# Schematic_esp-firework-firing-system-hw2.net
KiCad netlist of a schematic drawn in EasyEDA
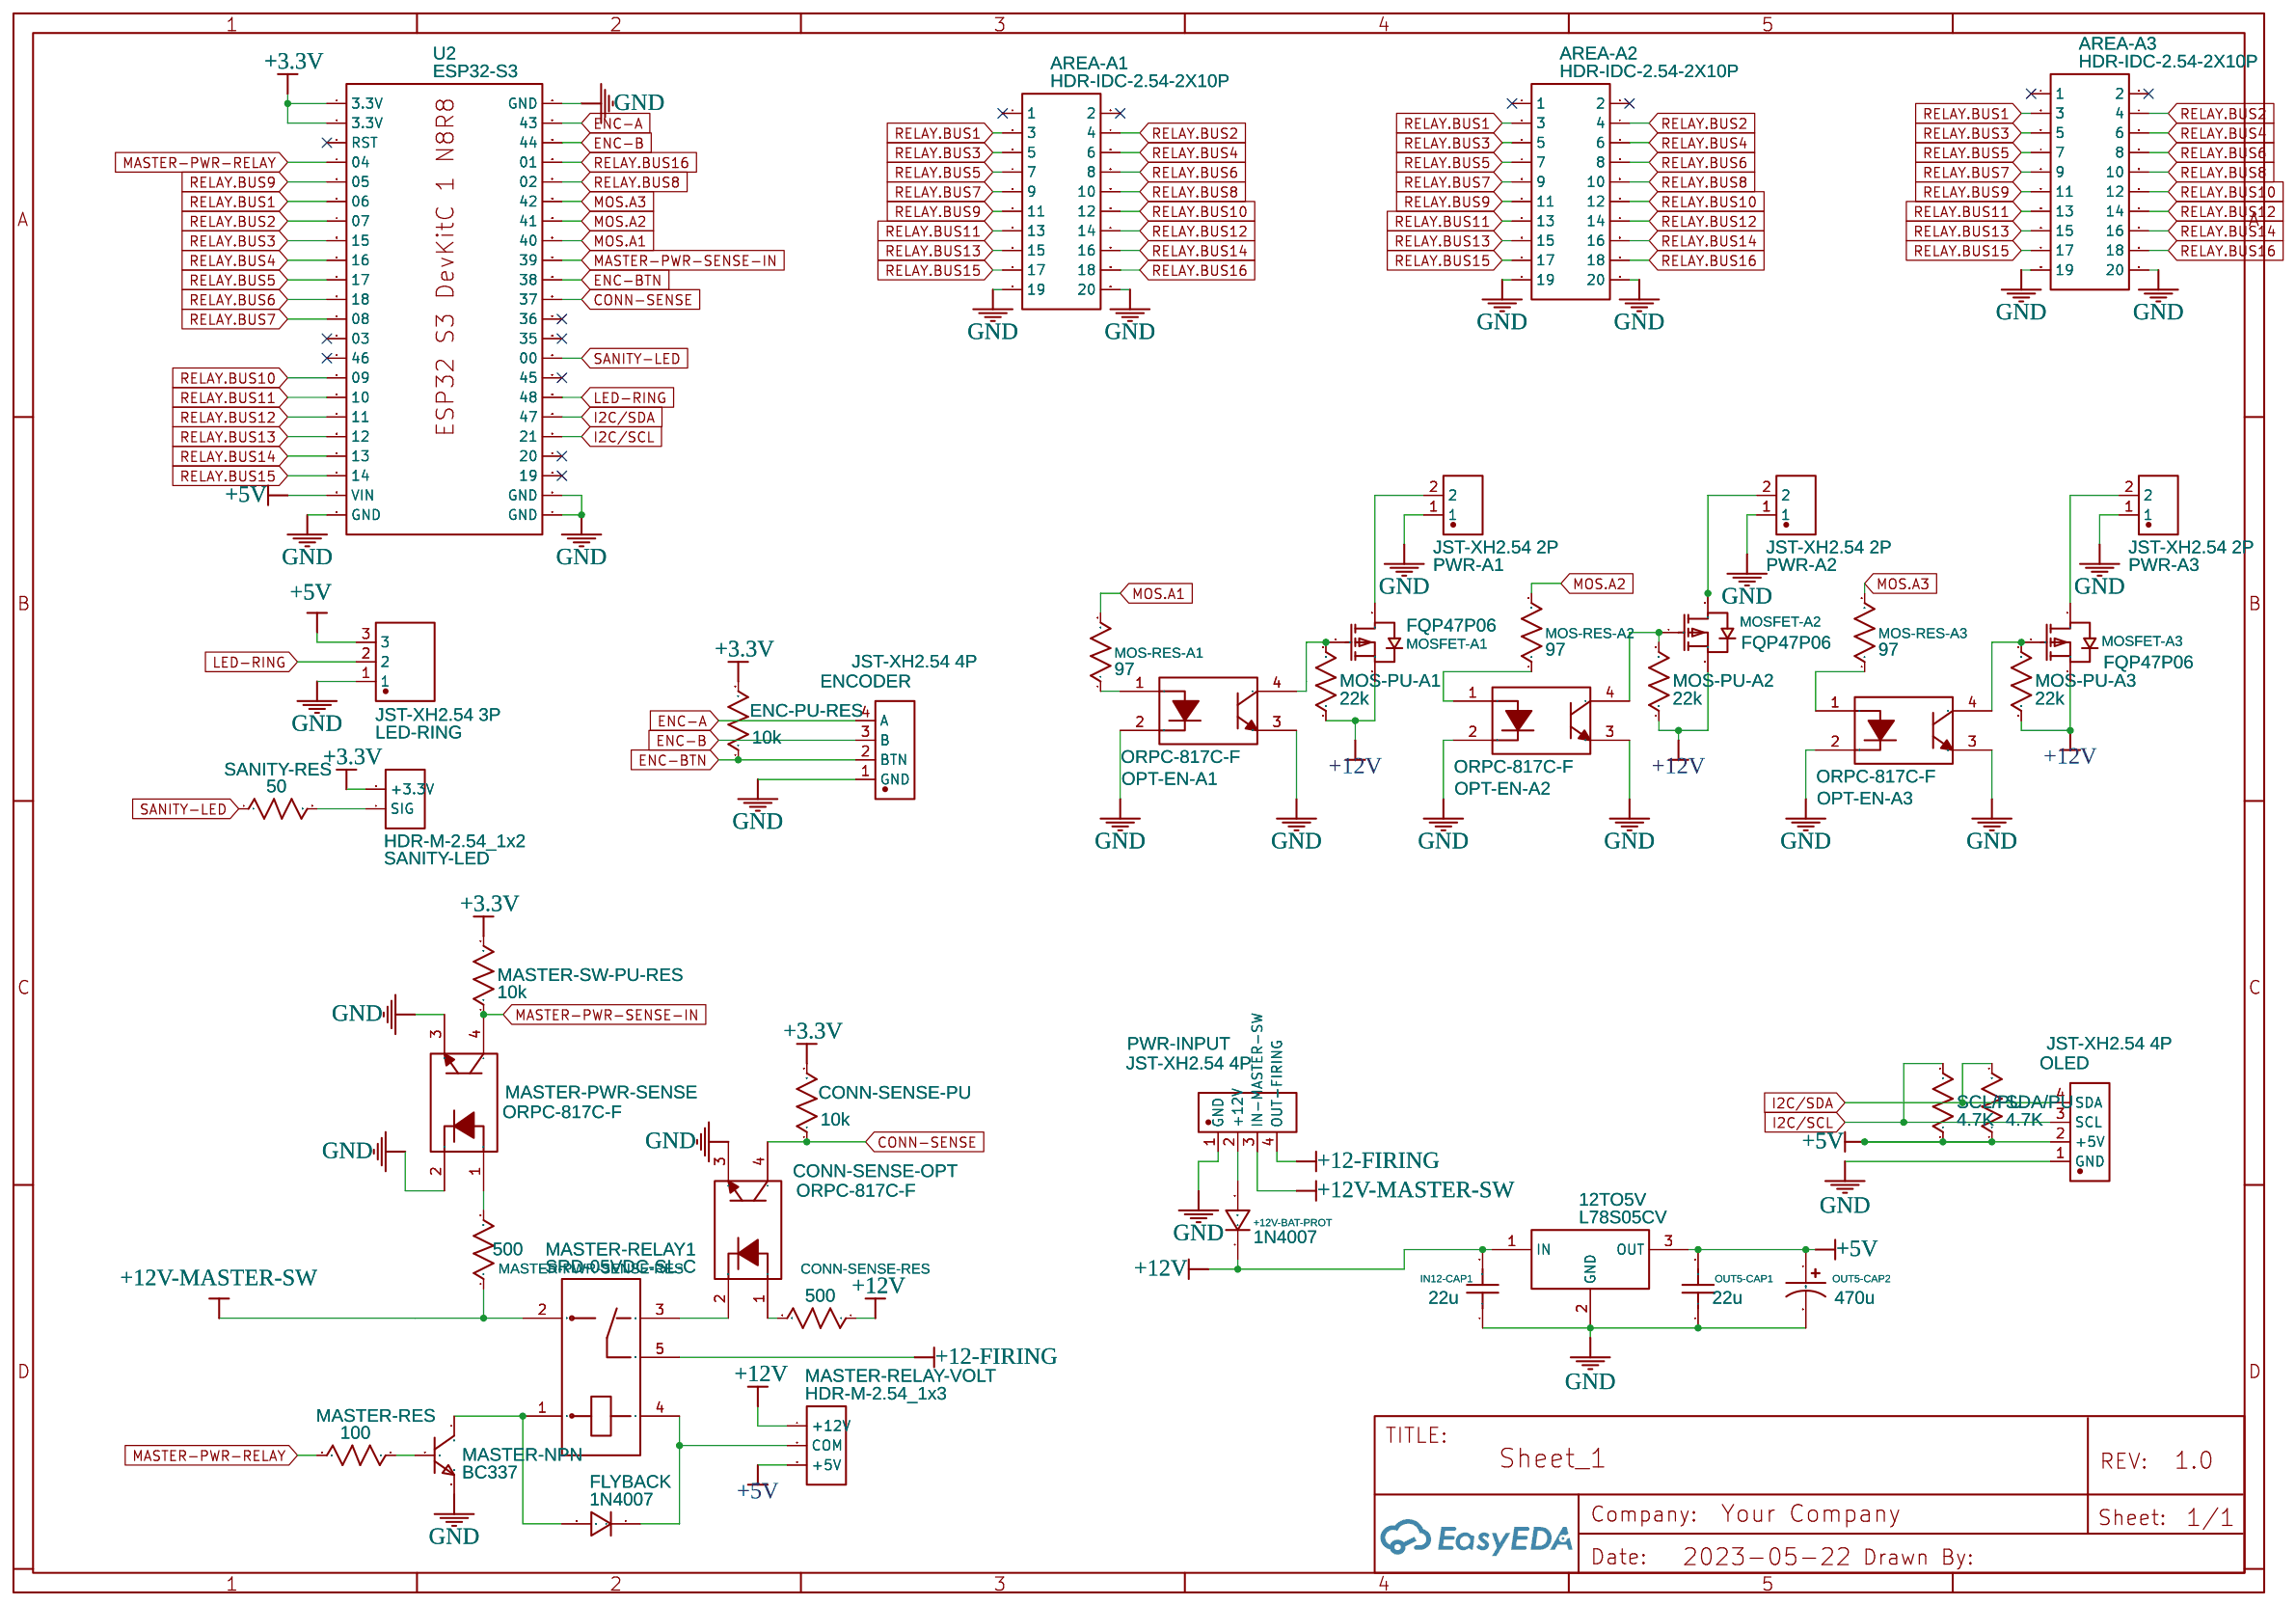
[diagram p0: schematic sheet]

(export (version "E")
  (design (tool "Eeschema 10.0.6"))
  (components
    (comp (ref "+12V-BAT-PROT")
      (value "1N4007")
      (fields (field (name "BOM_Supplier Part") "C106903"))
      (libsource (lib "") (part "1N4007"))
    )
    (comp (ref "12TO5V")
      (value "L78S05CV")
      (fields (field (name "BOM_Supplier Part") "C33043"))
      (libsource (lib "") (part "L78S05CV"))
    )
    (comp (ref "AREA-A1")
      (value "HDR-IDC-2.54-2X10P")
      (fields
        (field (name "BOM_Manufacturer Part") "IDC Box 2.54mm 2X10P　Straight")
        (field (name "BOM_Supplier Part") "C3405")
      )
      (libsource (lib "") (part "HDR-IDC-2.54-2X10P"))
    )
    (comp (ref "AREA-A2")
      (value "HDR-IDC-2.54-2X10P")
      (fields
        (field (name "BOM_Manufacturer Part") "IDC Box 2.54mm 2X10P　Straight")
        (field (name "BOM_Supplier Part") "C3405")
      )
      (libsource (lib "") (part "HDR-IDC-2.54-2X10P"))
    )
    (comp (ref "AREA-A3")
      (value "HDR-IDC-2.54-2X10P")
      (fields
        (field (name "BOM_Manufacturer Part") "IDC Box 2.54mm 2X10P　Straight")
        (field (name "BOM_Supplier Part") "C3405")
      )
      (libsource (lib "") (part "HDR-IDC-2.54-2X10P"))
    )
    (comp (ref "CONN-SENSE-OPT")
      (value "ORPC-817C-F")
      (fields (field (name "BOM_Supplier Part") "C2842770"))
      (libsource (lib "") (part "ORPC-817C-F_1"))
    )
    (comp (ref "CONN-SENSE-PU") (value "10k") (libsource (lib "") (part "R_AXIAL-0.3_US_7")))
    (comp (ref "CONN-SENSE-RES") (value "500") (libsource (lib "") (part "R_AXIAL-0.3_US_1")))
    (comp (ref "ENC-PU-RES") (value "10k") (libsource (lib "") (part "R_AXIAL-0.3_US_2")))
    (comp (ref "ENCODER") (value "JST-XH2.54 4P") (libsource (lib "") (part "JST-XH2.54 4P")))
    (comp (ref "FLYBACK")
      (value "1N4007")
      (fields (field (name "BOM_Supplier Part") "C106903"))
      (libsource (lib "") (part "1N4007_1"))
    )
    (comp (ref "IN12-CAP1") (value "22u") (libsource (lib "") (part "C_RAD-0.1_US")))
    (comp (ref "LED-RING") (value "JST-XH2.54 3P") (libsource (lib "") (part "JST-XH2.54 3P")))
    (comp (ref "MASTER-NPN") (value "BC337") (libsource (lib "") (part "BC337")))
    (comp (ref "MASTER-PWR-SENSE")
      (value "ORPC-817C-F")
      (fields (field (name "BOM_Supplier Part") "C2842770"))
      (libsource (lib "") (part "ORPC-817C-F_2"))
    )
    (comp (ref "MASTER-PWR-SENSE-RES") (value "500") (libsource (lib "") (part "R_AXIAL-0.3_US_10")))
    (comp (ref "MASTER-RELAY-VOLT")
      (value "HDR-M-2.54_1x3")
      (fields (field (name "BOM_Supplier Part") "C180248"))
      (libsource (lib "") (part "HDR-M-2.54_1x3"))
    )
    (comp (ref "MASTER-RELAY1")
      (value "SRD-05VDC-SL-C")
      (fields (field (name "BOM_Supplier Part") "C35449"))
      (libsource (lib "") (part "SRD-05VDC-SL-C"))
    )
    (comp (ref "MASTER-RES") (value "100") (libsource (lib "") (part "R_AXIAL-0.3_US_3")))
    (comp (ref "MASTER-SW-PU-RES") (value "10k") (libsource (lib "") (part "R_AXIAL-0.3_US_9")))
    (comp (ref "MOS-PU-A1") (value "22k") (libsource (lib "") (part "R_AXIAL-0.3_US")))
    (comp (ref "MOS-PU-A2") (value "22k") (libsource (lib "") (part "R_AXIAL-0.3_US")))
    (comp (ref "MOS-PU-A3") (value "22k") (libsource (lib "") (part "R_AXIAL-0.3_US")))
    (comp (ref "MOS-RES-A1") (value "97") (libsource (lib "") (part "R_AXIAL-0.3_US_4")))
    (comp (ref "MOS-RES-A2") (value "97") (libsource (lib "") (part "R_AXIAL-0.3_US_4")))
    (comp (ref "MOS-RES-A3") (value "97") (libsource (lib "") (part "R_AXIAL-0.3_US_4")))
    (comp (ref "MOSFET-A1")
      (value "FQP47P06")
      (fields (field (name "BOM_Supplier Part") "C462765"))
      (libsource (lib "") (part "FQP47P06"))
    )
    (comp (ref "MOSFET-A2")
      (value "FQP47P06")
      (fields (field (name "BOM_Supplier Part") "C462765"))
      (libsource (lib "") (part "FQP47P06"))
    )
    (comp (ref "MOSFET-A3")
      (value "FQP47P06")
      (fields (field (name "BOM_Supplier Part") "C462765"))
      (libsource (lib "") (part "FQP47P06"))
    )
    (comp (ref "OLED") (value "JST-XH2.54 4P") (libsource (lib "") (part "JST-XH2.54 4P_2")))
    (comp (ref "OPT-EN-A1")
      (value "ORPC-817C-F")
      (fields (field (name "BOM_Supplier Part") "C2842770"))
      (libsource (lib "") (part "ORPC-817C-F"))
    )
    (comp (ref "OPT-EN-A2")
      (value "ORPC-817C-F")
      (fields (field (name "BOM_Supplier Part") "C2842770"))
      (libsource (lib "") (part "ORPC-817C-F"))
    )
    (comp (ref "OPT-EN-A3")
      (value "ORPC-817C-F")
      (fields (field (name "BOM_Supplier Part") "C2842770"))
      (libsource (lib "") (part "ORPC-817C-F"))
    )
    (comp (ref "OUT5-CAP1") (value "22u") (libsource (lib "") (part "C_RAD-0.1_US_1")))
    (comp (ref "OUT5-CAP2") (value "470u") (libsource (lib "") (part "CE_TH_D6.3×F2.5_US")))
    (comp (ref "PWR-A1") (value "JST-XH2.54 2P") (libsource (lib "") (part "JST-XH2.54 2P")))
    (comp (ref "PWR-A2") (value "JST-XH2.54 2P") (libsource (lib "") (part "JST-XH2.54 2P")))
    (comp (ref "PWR-A3") (value "JST-XH2.54 2P") (libsource (lib "") (part "JST-XH2.54 2P")))
    (comp (ref "PWR-INPUT") (value "JST-XH2.54 4P") (libsource (lib "") (part "JST-XH2.54 4P_1")))
    (comp (ref "SANITY-LED")
      (value "HDR-M-2.54_1x2")
      (fields (field (name "BOM_Supplier Part") "C124375"))
      (libsource (lib "") (part "HDR-M-2.54_1x2"))
    )
    (comp (ref "SANITY-RES") (value "50") (libsource (lib "") (part "R_AXIAL-0.3_US_8")))
    (comp (ref "SCL/PU") (value "4.7K") (libsource (lib "") (part "R_AXIAL-0.3_US_5")))
    (comp (ref "SDA/PU") (value "4.7K") (libsource (lib "") (part "R_AXIAL-0.3_US_6")))
    (comp (ref "U2") (value "ESP32-S3") (libsource (lib "") (part "ESP32-S3")))
  )
  (nets
    (net (code "1") (name "+3.3V") (class "Default")
      (node (ref "CONN-SENSE-PU") (pin "2") (pinfunction "2_2") (pintype "unspecified"))
      (node (ref "ENC-PU-RES") (pin "2") (pinfunction "2_2") (pintype "unspecified"))
      (node (ref "MASTER-SW-PU-RES") (pin "2") (pinfunction "2_2") (pintype "unspecified"))
      (node (ref "SANITY-LED") (pin "2") (pinfunction "+3.3V_2") (pintype "unspecified"))
      (node (ref "U2") (pin "1") (pinfunction "3.3V_1") (pintype "unspecified"))
      (node (ref "U2") (pin "2") (pinfunction "3.3V_2") (pintype "unspecified"))
    )
    (net (code "2") (name "+5V") (class "Default")
      (node (ref "12TO5V") (pin "3") (pinfunction "OUT_3") (pintype "passive"))
      (node (ref "LED-RING") (pin "3") (pinfunction "3_3") (pintype "unspecified"))
      (node (ref "MASTER-RELAY-VOLT") (pin "3") (pinfunction "+5V_3") (pintype "input"))
      (node (ref "OLED") (pin "2") (pinfunction "+5V_2") (pintype "unspecified"))
      (node (ref "OUT5-CAP1") (pin "2") (pinfunction "2_2") (pintype "unspecified"))
      (node (ref "OUT5-CAP2") (pin "1") (pinfunction "1_1") (pintype "unspecified"))
      (node (ref "SCL/PU") (pin "1") (pinfunction "1_1") (pintype "unspecified"))
      (node (ref "SDA/PU") (pin "1") (pinfunction "1_1") (pintype "unspecified"))
      (node (ref "U2") (pin "21") (pinfunction "VIN_21") (pintype "unspecified"))
    )
    (net (code "3") (name "+12-FIRING") (class "Default")
      (node (ref "MASTER-RELAY1") (pin "5") (pinfunction "5_5") (pintype "input"))
      (node (ref "PWR-INPUT") (pin "4") (pinfunction "OUT-FIRING_4") (pintype "unspecified"))
    )
    (net (code "4") (name "+12V") (class "Default")
      (node (ref "+12V-BAT-PROT") (pin "1") (pinfunction "1_1") (pintype "unspecified"))
      (node (ref "12TO5V") (pin "1") (pinfunction "IN_1") (pintype "passive"))
      (node (ref "CONN-SENSE-RES") (pin "1") (pinfunction "1_1") (pintype "unspecified"))
      (node (ref "IN12-CAP1") (pin "2") (pinfunction "2_2") (pintype "unspecified"))
      (node (ref "MASTER-RELAY-VOLT") (pin "1") (pinfunction "+12V_1") (pintype "input"))
      (node (ref "MOS-PU-A1") (pin "1") (pinfunction "1_1") (pintype "unspecified"))
      (node (ref "MOS-PU-A2") (pin "1") (pinfunction "1_1") (pintype "unspecified"))
      (node (ref "MOS-PU-A3") (pin "1") (pinfunction "1_1") (pintype "unspecified"))
      (node (ref "MOSFET-A1") (pin "3") (pinfunction "S_3") (pintype "unspecified"))
      (node (ref "MOSFET-A2") (pin "3") (pinfunction "S_3") (pintype "unspecified"))
      (node (ref "MOSFET-A3") (pin "3") (pinfunction "S_3") (pintype "unspecified"))
    )
    (net (code "5") (name "+12V-MASTER-SW") (class "Default")
      (node (ref "MASTER-PWR-SENSE-RES") (pin "1") (pinfunction "1_1") (pintype "unspecified"))
      (node (ref "MASTER-RELAY1") (pin "2") (pinfunction "2_2") (pintype "input"))
      (node (ref "PWR-INPUT") (pin "3") (pinfunction "IN-MASTER-SW_3") (pintype "unspecified"))
    )
    (net (code "6") (name "CONN-SENSE") (class "Default")
      (node (ref "CONN-SENSE-OPT") (pin "4") (pinfunction "4_4") (pintype "unspecified"))
      (node (ref "CONN-SENSE-PU") (pin "1") (pinfunction "1_1") (pintype "unspecified"))
      (node (ref "U2") (pin "33") (pinfunction "37_33") (pintype "unspecified"))
    )
    (net (code "7") (name "ENC-A") (class "Default")
      (node (ref "ENCODER") (pin "4") (pinfunction "A_4") (pintype "unspecified"))
      (node (ref "U2") (pin "24") (pinfunction "43_24") (pintype "unspecified"))
    )
    (net (code "8") (name "ENC-B") (class "Default")
      (node (ref "ENCODER") (pin "3") (pinfunction "B_3") (pintype "unspecified"))
      (node (ref "U2") (pin "25") (pinfunction "44_25") (pintype "unspecified"))
    )
    (net (code "9") (name "ENC-BTN") (class "Default")
      (node (ref "ENC-PU-RES") (pin "1") (pinfunction "1_1") (pintype "unspecified"))
      (node (ref "ENCODER") (pin "2") (pinfunction "BTN_2") (pintype "unspecified"))
      (node (ref "U2") (pin "32") (pinfunction "38_32") (pintype "unspecified"))
    )
    (net (code "10") (name "GND") (class "Default")
      (node (ref "12TO5V") (pin "2") (pinfunction "GND_2") (pintype "passive"))
      (node (ref "AREA-A1") (pin "19") (pinfunction "19_19") (pintype "unspecified"))
      (node (ref "AREA-A1") (pin "20") (pinfunction "20_20") (pintype "unspecified"))
      (node (ref "AREA-A2") (pin "19") (pinfunction "19_19") (pintype "unspecified"))
      (node (ref "AREA-A2") (pin "20") (pinfunction "20_20") (pintype "unspecified"))
      (node (ref "AREA-A3") (pin "19") (pinfunction "19_19") (pintype "unspecified"))
      (node (ref "AREA-A3") (pin "20") (pinfunction "20_20") (pintype "unspecified"))
      (node (ref "CONN-SENSE-OPT") (pin "3") (pinfunction "3_3") (pintype "unspecified"))
      (node (ref "ENCODER") (pin "1") (pinfunction "GND_1") (pintype "unspecified"))
      (node (ref "IN12-CAP1") (pin "1") (pinfunction "1_1") (pintype "unspecified"))
      (node (ref "LED-RING") (pin "1") (pinfunction "1_1") (pintype "unspecified"))
      (node (ref "MASTER-NPN") (pin "3") (pinfunction "E_3") (pintype "unspecified"))
      (node (ref "MASTER-PWR-SENSE") (pin "2") (pinfunction "2_2") (pintype "unspecified"))
      (node (ref "MASTER-PWR-SENSE") (pin "3") (pinfunction "3_3") (pintype "unspecified"))
      (node (ref "OLED") (pin "1") (pinfunction "GND_1") (pintype "unspecified"))
      (node (ref "OPT-EN-A1") (pin "2") (pinfunction "2_2") (pintype "unspecified"))
      (node (ref "OPT-EN-A1") (pin "3") (pinfunction "3_3") (pintype "unspecified"))
      (node (ref "OPT-EN-A2") (pin "2") (pinfunction "2_2") (pintype "unspecified"))
      (node (ref "OPT-EN-A2") (pin "3") (pinfunction "3_3") (pintype "unspecified"))
      (node (ref "OPT-EN-A3") (pin "2") (pinfunction "2_2") (pintype "unspecified"))
      (node (ref "OPT-EN-A3") (pin "3") (pinfunction "3_3") (pintype "unspecified"))
      (node (ref "OUT5-CAP1") (pin "1") (pinfunction "1_1") (pintype "unspecified"))
      (node (ref "OUT5-CAP2") (pin "2") (pinfunction "2_2") (pintype "unspecified"))
      (node (ref "PWR-A1") (pin "1") (pinfunction "1_1") (pintype "unspecified"))
      (node (ref "PWR-A2") (pin "1") (pinfunction "1_1") (pintype "unspecified"))
      (node (ref "PWR-A3") (pin "1") (pinfunction "1_1") (pintype "unspecified"))
      (node (ref "PWR-INPUT") (pin "1") (pinfunction "GND_1") (pintype "unspecified"))
      (node (ref "U2") (pin "22") (pinfunction "GND_22") (pintype "unspecified"))
      (node (ref "U2") (pin "23") (pinfunction "GND_23") (pintype "unspecified"))
      (node (ref "U2") (pin "43") (pinfunction "GND_43") (pintype "unspecified"))
      (node (ref "U2") (pin "44") (pinfunction "GND_44") (pintype "unspecified"))
    )
    (net (code "11") (name "I2C{slash}SCL") (class "Default")
      (node (ref "OLED") (pin "3") (pinfunction "SCL_3") (pintype "unspecified"))
      (node (ref "SCL/PU") (pin "2") (pinfunction "2_2") (pintype "unspecified"))
      (node (ref "U2") (pin "40") (pinfunction "21_40") (pintype "unspecified"))
    )
    (net (code "12") (name "I2C{slash}SDA") (class "Default")
      (node (ref "OLED") (pin "4") (pinfunction "SDA_4") (pintype "unspecified"))
      (node (ref "SDA/PU") (pin "2") (pinfunction "2_2") (pintype "unspecified"))
      (node (ref "U2") (pin "39") (pinfunction "47_39") (pintype "unspecified"))
    )
    (net (code "13") (name "LED-RING") (class "Default")
      (node (ref "LED-RING") (pin "2") (pinfunction "2_2") (pintype "unspecified"))
      (node (ref "U2") (pin "38") (pinfunction "48_38") (pintype "unspecified"))
    )
    (net (code "14") (name "MASTER-PWR-RELAY") (class "Default")
      (node (ref "MASTER-RES") (pin "2") (pinfunction "2_2") (pintype "unspecified"))
      (node (ref "U2") (pin "4") (pinfunction "04_4") (pintype "unspecified"))
    )
    (net (code "15") (name "MASTER-PWR-SENSE-IN") (class "Default")
      (node (ref "MASTER-PWR-SENSE") (pin "4") (pinfunction "4_4") (pintype "unspecified"))
      (node (ref "MASTER-SW-PU-RES") (pin "1") (pinfunction "1_1") (pintype "unspecified"))
      (node (ref "U2") (pin "31") (pinfunction "39_31") (pintype "unspecified"))
    )
    (net (code "16") (name "MOS.A1") (class "Default")
      (node (ref "MOS-RES-A1") (pin "2") (pinfunction "2_2") (pintype "unspecified"))
      (node (ref "U2") (pin "30") (pinfunction "40_30") (pintype "unspecified"))
    )
    (net (code "17") (name "MOS.A2") (class "Default")
      (node (ref "MOS-RES-A2") (pin "2") (pinfunction "2_2") (pintype "unspecified"))
      (node (ref "U2") (pin "29") (pinfunction "41_29") (pintype "unspecified"))
    )
    (net (code "18") (name "MOS.A3") (class "Default")
      (node (ref "MOS-RES-A3") (pin "2") (pinfunction "2_2") (pintype "unspecified"))
      (node (ref "U2") (pin "28") (pinfunction "42_28") (pintype "unspecified"))
    )
    (net (code "19") (name "Net-(CONN-SENSE-OPT-Pad1)") (class "Default")
      (node (ref "CONN-SENSE-OPT") (pin "1") (pinfunction "1_1") (pintype "unspecified"))
      (node (ref "CONN-SENSE-RES") (pin "2") (pinfunction "2_2") (pintype "unspecified"))
    )
    (net (code "20") (name "Net-(CONN-SENSE-OPT-Pad2)") (class "Default")
      (node (ref "CONN-SENSE-OPT") (pin "2") (pinfunction "2_2") (pintype "unspecified"))
      (node (ref "MASTER-RELAY1") (pin "3") (pinfunction "3_3") (pintype "input"))
    )
    (net (code "21") (name "Net-(MASTER-NPN-B)") (class "Default")
      (node (ref "MASTER-NPN") (pin "2") (pinfunction "B_2") (pintype "unspecified"))
      (node (ref "MASTER-RES") (pin "1") (pinfunction "1_1") (pintype "unspecified"))
    )
    (net (code "22") (name "Net-(MASTER-NPN-C)") (class "Default")
      (node (ref "FLYBACK") (pin "2") (pinfunction "2_2") (pintype "unspecified"))
      (node (ref "MASTER-NPN") (pin "1") (pinfunction "C_1") (pintype "unspecified"))
      (node (ref "MASTER-RELAY1") (pin "1") (pinfunction "1_1") (pintype "input"))
    )
    (net (code "23") (name "Net-(MASTER-PWR-SENSE-Pad1)") (class "Default")
      (node (ref "MASTER-PWR-SENSE") (pin "1") (pinfunction "1_1") (pintype "unspecified"))
      (node (ref "MASTER-PWR-SENSE-RES") (pin "2") (pinfunction "2_2") (pintype "unspecified"))
    )
    (net (code "24") (name "Net-(MASTER-RELAY-VOLT-COM)") (class "Default")
      (node (ref "FLYBACK") (pin "1") (pinfunction "1_1") (pintype "unspecified"))
      (node (ref "MASTER-RELAY-VOLT") (pin "2") (pinfunction "COM_2") (pintype "input"))
      (node (ref "MASTER-RELAY1") (pin "4") (pinfunction "4_4") (pintype "input"))
    )
    (net (code "25") (name "Net-(MOS-RES-A1-Pad1)") (class "Default")
      (node (ref "MOS-RES-A1") (pin "1") (pinfunction "1_1") (pintype "unspecified"))
      (node (ref "OPT-EN-A1") (pin "1") (pinfunction "1_1") (pintype "unspecified"))
    )
    (net (code "26") (name "Net-(MOS-RES-A2-Pad1)") (class "Default")
      (node (ref "MOS-RES-A2") (pin "1") (pinfunction "1_1") (pintype "unspecified"))
      (node (ref "OPT-EN-A2") (pin "1") (pinfunction "1_1") (pintype "unspecified"))
    )
    (net (code "27") (name "Net-(MOS-RES-A3-Pad1)") (class "Default")
      (node (ref "MOS-RES-A3") (pin "1") (pinfunction "1_1") (pintype "unspecified"))
      (node (ref "OPT-EN-A3") (pin "1") (pinfunction "1_1") (pintype "unspecified"))
    )
    (net (code "28") (name "Net-(MOSFET-A1-D)") (class "Default")
      (node (ref "MOSFET-A1") (pin "2") (pinfunction "D_2") (pintype "unspecified"))
      (node (ref "PWR-A1") (pin "2") (pinfunction "2_2") (pintype "unspecified"))
    )
    (net (code "29") (name "Net-(MOSFET-A1-G)") (class "Default")
      (node (ref "MOS-PU-A1") (pin "2") (pinfunction "2_2") (pintype "unspecified"))
      (node (ref "MOSFET-A1") (pin "1") (pinfunction "G_1") (pintype "unspecified"))
      (node (ref "OPT-EN-A1") (pin "4") (pinfunction "4_4") (pintype "unspecified"))
    )
    (net (code "30") (name "Net-(MOSFET-A2-D)") (class "Default")
      (node (ref "MOSFET-A2") (pin "2") (pinfunction "D_2") (pintype "unspecified"))
      (node (ref "PWR-A2") (pin "2") (pinfunction "2_2") (pintype "unspecified"))
    )
    (net (code "31") (name "Net-(MOSFET-A2-G)") (class "Default")
      (node (ref "MOS-PU-A2") (pin "2") (pinfunction "2_2") (pintype "unspecified"))
      (node (ref "MOSFET-A2") (pin "1") (pinfunction "G_1") (pintype "unspecified"))
      (node (ref "OPT-EN-A2") (pin "4") (pinfunction "4_4") (pintype "unspecified"))
    )
    (net (code "32") (name "Net-(MOSFET-A3-D)") (class "Default")
      (node (ref "MOSFET-A3") (pin "2") (pinfunction "D_2") (pintype "unspecified"))
      (node (ref "PWR-A3") (pin "2") (pinfunction "2_2") (pintype "unspecified"))
    )
    (net (code "33") (name "Net-(MOSFET-A3-G)") (class "Default")
      (node (ref "MOS-PU-A3") (pin "2") (pinfunction "2_2") (pintype "unspecified"))
      (node (ref "MOSFET-A3") (pin "1") (pinfunction "G_1") (pintype "unspecified"))
      (node (ref "OPT-EN-A3") (pin "4") (pinfunction "4_4") (pintype "unspecified"))
    )
    (net (code "34") (name "Net-(PWR-INPUT-+12V)") (class "Default")
      (node (ref "+12V-BAT-PROT") (pin "2") (pinfunction "2_2") (pintype "unspecified"))
      (node (ref "PWR-INPUT") (pin "2") (pinfunction "+12V_2") (pintype "unspecified"))
    )
    (net (code "35") (name "Net-(SANITY-LED-SIG)") (class "Default")
      (node (ref "SANITY-LED") (pin "1") (pinfunction "SIG_1") (pintype "unspecified"))
      (node (ref "SANITY-RES") (pin "2") (pinfunction "2_2") (pintype "unspecified"))
    )
    (net (code "36") (name "RELAY.BUS1") (class "Default")
      (node (ref "AREA-A1") (pin "3") (pinfunction "3_3") (pintype "unspecified"))
      (node (ref "AREA-A2") (pin "3") (pinfunction "3_3") (pintype "unspecified"))
      (node (ref "AREA-A3") (pin "3") (pinfunction "3_3") (pintype "unspecified"))
      (node (ref "U2") (pin "6") (pinfunction "06_6") (pintype "unspecified"))
    )
    (net (code "37") (name "RELAY.BUS2") (class "Default")
      (node (ref "AREA-A1") (pin "4") (pinfunction "4_4") (pintype "unspecified"))
      (node (ref "AREA-A2") (pin "4") (pinfunction "4_4") (pintype "unspecified"))
      (node (ref "AREA-A3") (pin "4") (pinfunction "4_4") (pintype "unspecified"))
      (node (ref "U2") (pin "7") (pinfunction "07_7") (pintype "unspecified"))
    )
    (net (code "38") (name "RELAY.BUS3") (class "Default")
      (node (ref "AREA-A1") (pin "5") (pinfunction "5_5") (pintype "unspecified"))
      (node (ref "AREA-A2") (pin "5") (pinfunction "5_5") (pintype "unspecified"))
      (node (ref "AREA-A3") (pin "5") (pinfunction "5_5") (pintype "unspecified"))
      (node (ref "U2") (pin "8") (pinfunction "15_8") (pintype "unspecified"))
    )
    (net (code "39") (name "RELAY.BUS4") (class "Default")
      (node (ref "AREA-A1") (pin "6") (pinfunction "6_6") (pintype "unspecified"))
      (node (ref "AREA-A2") (pin "6") (pinfunction "6_6") (pintype "unspecified"))
      (node (ref "AREA-A3") (pin "6") (pinfunction "6_6") (pintype "unspecified"))
      (node (ref "U2") (pin "9") (pinfunction "16_9") (pintype "unspecified"))
    )
    (net (code "40") (name "RELAY.BUS5") (class "Default")
      (node (ref "AREA-A1") (pin "7") (pinfunction "7_7") (pintype "unspecified"))
      (node (ref "AREA-A2") (pin "7") (pinfunction "7_7") (pintype "unspecified"))
      (node (ref "AREA-A3") (pin "7") (pinfunction "7_7") (pintype "unspecified"))
      (node (ref "U2") (pin "10") (pinfunction "17_10") (pintype "unspecified"))
    )
    (net (code "41") (name "RELAY.BUS6") (class "Default")
      (node (ref "AREA-A1") (pin "8") (pinfunction "8_8") (pintype "unspecified"))
      (node (ref "AREA-A2") (pin "8") (pinfunction "8_8") (pintype "unspecified"))
      (node (ref "AREA-A3") (pin "8") (pinfunction "8_8") (pintype "unspecified"))
      (node (ref "U2") (pin "11") (pinfunction "18_11") (pintype "unspecified"))
    )
    (net (code "42") (name "RELAY.BUS7") (class "Default")
      (node (ref "AREA-A1") (pin "9") (pinfunction "9_9") (pintype "unspecified"))
      (node (ref "AREA-A2") (pin "9") (pinfunction "9_9") (pintype "unspecified"))
      (node (ref "AREA-A3") (pin "9") (pinfunction "9_9") (pintype "unspecified"))
      (node (ref "U2") (pin "12") (pinfunction "08_12") (pintype "unspecified"))
    )
    (net (code "43") (name "RELAY.BUS8") (class "Default")
      (node (ref "AREA-A1") (pin "10") (pinfunction "10_10") (pintype "unspecified"))
      (node (ref "AREA-A2") (pin "10") (pinfunction "10_10") (pintype "unspecified"))
      (node (ref "AREA-A3") (pin "10") (pinfunction "10_10") (pintype "unspecified"))
      (node (ref "U2") (pin "27") (pinfunction "02_27") (pintype "unspecified"))
    )
    (net (code "44") (name "RELAY.BUS9") (class "Default")
      (node (ref "AREA-A1") (pin "11") (pinfunction "11_11") (pintype "unspecified"))
      (node (ref "AREA-A2") (pin "11") (pinfunction "11_11") (pintype "unspecified"))
      (node (ref "AREA-A3") (pin "11") (pinfunction "11_11") (pintype "unspecified"))
      (node (ref "U2") (pin "5") (pinfunction "05_5") (pintype "unspecified"))
    )
    (net (code "45") (name "RELAY.BUS10") (class "Default")
      (node (ref "AREA-A1") (pin "12") (pinfunction "12_12") (pintype "unspecified"))
      (node (ref "AREA-A2") (pin "12") (pinfunction "12_12") (pintype "unspecified"))
      (node (ref "AREA-A3") (pin "12") (pinfunction "12_12") (pintype "unspecified"))
      (node (ref "U2") (pin "15") (pinfunction "09_15") (pintype "unspecified"))
    )
    (net (code "46") (name "RELAY.BUS11") (class "Default")
      (node (ref "AREA-A1") (pin "13") (pinfunction "13_13") (pintype "unspecified"))
      (node (ref "AREA-A2") (pin "13") (pinfunction "13_13") (pintype "unspecified"))
      (node (ref "AREA-A3") (pin "13") (pinfunction "13_13") (pintype "unspecified"))
      (node (ref "U2") (pin "16") (pinfunction "10_16") (pintype "unspecified"))
    )
    (net (code "47") (name "RELAY.BUS12") (class "Default")
      (node (ref "AREA-A1") (pin "14") (pinfunction "14_14") (pintype "unspecified"))
      (node (ref "AREA-A2") (pin "14") (pinfunction "14_14") (pintype "unspecified"))
      (node (ref "AREA-A3") (pin "14") (pinfunction "14_14") (pintype "unspecified"))
      (node (ref "U2") (pin "17") (pinfunction "11_17") (pintype "unspecified"))
    )
    (net (code "48") (name "RELAY.BUS13") (class "Default")
      (node (ref "AREA-A1") (pin "15") (pinfunction "15_15") (pintype "unspecified"))
      (node (ref "AREA-A2") (pin "15") (pinfunction "15_15") (pintype "unspecified"))
      (node (ref "AREA-A3") (pin "15") (pinfunction "15_15") (pintype "unspecified"))
      (node (ref "U2") (pin "18") (pinfunction "12_18") (pintype "unspecified"))
    )
    (net (code "49") (name "RELAY.BUS14") (class "Default")
      (node (ref "AREA-A1") (pin "16") (pinfunction "16_16") (pintype "unspecified"))
      (node (ref "AREA-A2") (pin "16") (pinfunction "16_16") (pintype "unspecified"))
      (node (ref "AREA-A3") (pin "16") (pinfunction "16_16") (pintype "unspecified"))
      (node (ref "U2") (pin "19") (pinfunction "13_19") (pintype "unspecified"))
    )
    (net (code "50") (name "RELAY.BUS15") (class "Default")
      (node (ref "AREA-A1") (pin "17") (pinfunction "17_17") (pintype "unspecified"))
      (node (ref "AREA-A2") (pin "17") (pinfunction "17_17") (pintype "unspecified"))
      (node (ref "AREA-A3") (pin "17") (pinfunction "17_17") (pintype "unspecified"))
      (node (ref "U2") (pin "20") (pinfunction "14_20") (pintype "unspecified"))
    )
    (net (code "51") (name "RELAY.BUS16") (class "Default")
      (node (ref "AREA-A1") (pin "18") (pinfunction "18_18") (pintype "unspecified"))
      (node (ref "AREA-A2") (pin "18") (pinfunction "18_18") (pintype "unspecified"))
      (node (ref "AREA-A3") (pin "18") (pinfunction "18_18") (pintype "unspecified"))
      (node (ref "U2") (pin "26") (pinfunction "01_26") (pintype "unspecified"))
    )
    (net (code "52") (name "SANITY-LED") (class "Default")
      (node (ref "SANITY-RES") (pin "1") (pinfunction "1_1") (pintype "unspecified"))
      (node (ref "U2") (pin "36") (pinfunction "00_36") (pintype "unspecified"))
    )
    (net (code "53") (name "unconnected-(AREA-A1-Pad1)") (class "Default")
      (node (ref "AREA-A1") (pin "1") (pinfunction "1_1") (pintype "unspecified+no_connect"))
    )
    (net (code "54") (name "unconnected-(AREA-A1-Pad2)") (class "Default")
      (node (ref "AREA-A1") (pin "2") (pinfunction "2_2") (pintype "unspecified+no_connect"))
    )
    (net (code "55") (name "unconnected-(AREA-A2-Pad1)") (class "Default")
      (node (ref "AREA-A2") (pin "1") (pinfunction "1_1") (pintype "unspecified+no_connect"))
    )
    (net (code "56") (name "unconnected-(AREA-A2-Pad2)") (class "Default")
      (node (ref "AREA-A2") (pin "2") (pinfunction "2_2") (pintype "unspecified+no_connect"))
    )
    (net (code "57") (name "unconnected-(AREA-A3-Pad1)") (class "Default")
      (node (ref "AREA-A3") (pin "1") (pinfunction "1_1") (pintype "unspecified+no_connect"))
    )
    (net (code "58") (name "unconnected-(AREA-A3-Pad2)") (class "Default")
      (node (ref "AREA-A3") (pin "2") (pinfunction "2_2") (pintype "unspecified+no_connect"))
    )
    (net (code "59") (name "unconnected-(U2-03-Pad13)") (class "Default")
      (node (ref "U2") (pin "13") (pinfunction "03_13") (pintype "unspecified+no_connect"))
    )
    (net (code "60") (name "unconnected-(U2-19-Pad42)") (class "Default")
      (node (ref "U2") (pin "42") (pinfunction "19_42") (pintype "unspecified+no_connect"))
    )
    (net (code "61") (name "unconnected-(U2-20-Pad41)") (class "Default")
      (node (ref "U2") (pin "41") (pinfunction "20_41") (pintype "unspecified+no_connect"))
    )
    (net (code "62") (name "unconnected-(U2-36-Pad34)") (class "Default")
      (node (ref "U2") (pin "34") (pinfunction "36_34") (pintype "unspecified+no_connect"))
    )
    (net (code "63") (name "unconnected-(U2-45-Pad37)") (class "Default")
      (node (ref "U2") (pin "37") (pinfunction "45_37") (pintype "unspecified+no_connect"))
    )
    (net (code "64") (name "unconnected-(U2-46-Pad14)") (class "Default")
      (node (ref "U2") (pin "14") (pinfunction "46_14") (pintype "unspecified+no_connect"))
    )
    (net (code "65") (name "unconnected-(U2-Pad35)") (class "Default")
      (node (ref "U2") (pin "35") (pinfunction "35_35") (pintype "unspecified+no_connect"))
    )
    (net (code "66") (name "unconnected-(U2-RST-Pad3)") (class "Default")
      (node (ref "U2") (pin "3") (pinfunction "RST_3") (pintype "unspecified+no_connect"))
    )
  )
)
